# 03_ZIGBEE.net
KiCad netlist of a schematic drawn in Altium Designer
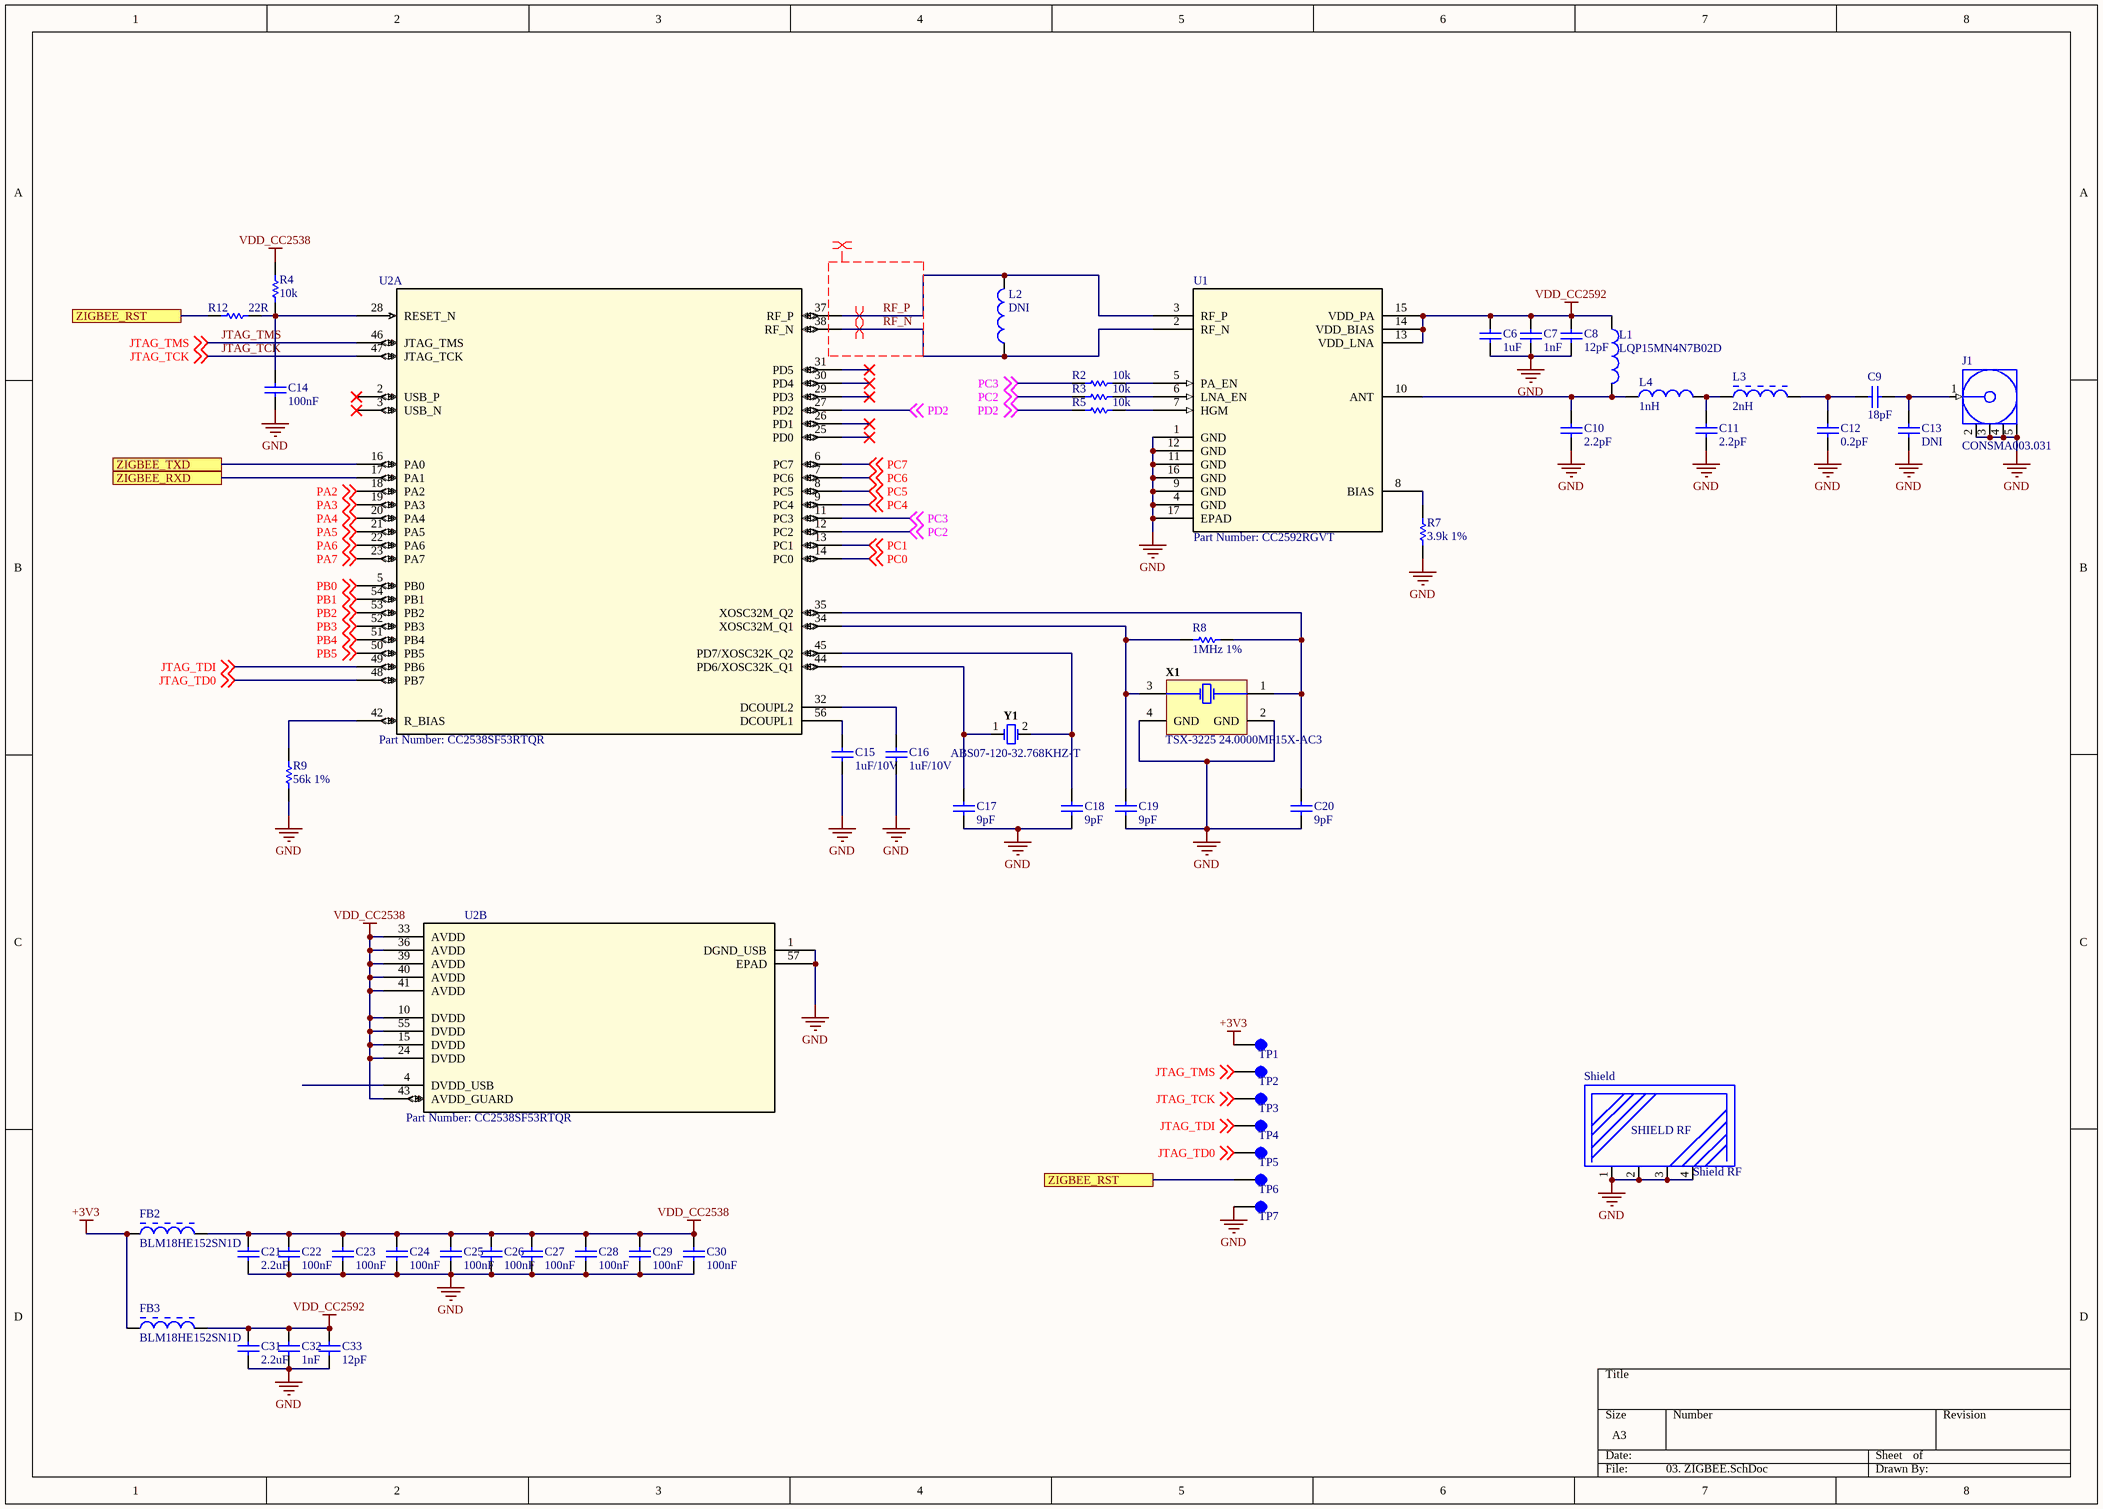
[diagram p0: 03. ZIGBEE.SchDoc]

(export (version "E")
  (design (tool "Eeschema 10.0.6"))
  (components
    (comp (ref "C6")
      (value "1uF")
      (footprint "CAPC1608X90X20NL10")
      (description "Chip Capacitor, 1 uF, +/- 10%, 50 V, -55 to 85 degC, 0603 (1608 Metric), RoHS, Tape and Reel")
      (fields
        (field (name "MANUFACTURER") "TDK")
        (field (name "PCN PART NUMBER") "MLCCPartNumberChange30/Nov/2012")
      )
      (libsource (lib "Altium Content Vault") (part "CAP-NP-2"))
    )
    (comp (ref "C7")
      (value "1nF")
      (footprint "CAPC1005X55X25NL05T10")
      (fields (field (name "PART NUMBER") "GRM1555C1H102JA01D") (field (name "MANUFACTURER") "Murata"))
      (libsource (lib "Altium Content Vault") (part "CAP"))
    )
    (comp (ref "C8")
      (value "12pF")
      (footprint "CAPC1005X55X25NL05T10")
      (fields (field (name "PART NUMBER") "GRM1555C1H120GA01D") (field (name "MANUFACTURER") "Murata"))
      (libsource (lib "Altium Content Vault") (part "CAP"))
    )
    (comp (ref "C9")
      (value "18pF")
      (footprint "CAPC1005X55X25NL05T10")
      (fields (field (name "PART NUMBER") "GJM1555C1H180GB01D") (field (name "MANUFACTURER") "Murata"))
      (libsource (lib "Altium Content Vault") (part "CAP"))
    )
    (comp (ref "C10")
      (value "2.2pF")
      (footprint "CAPC1005X55X25NL05T10")
      (fields (field (name "PART NUMBER") "GJM1555C1H2R2BB01D") (field (name "MANUFACTURER") "Murata"))
      (libsource (lib "Altium Content Vault") (part "CAP"))
    )
    (comp (ref "C11")
      (value "2.2pF")
      (footprint "CAPC1005X55X25NL05T10")
      (fields (field (name "PART NUMBER") "GJM1555C1H2R2BB01D") (field (name "MANUFACTURER") "Murata"))
      (libsource (lib "Altium Content Vault") (part "CAP"))
    )
    (comp (ref "C12")
      (value "0.2pF")
      (footprint "CAPC1005X55X25NL05T10")
      (fields (field (name "PART NUMBER") "GRM1555C1HR20WA01D") (field (name "MANUFACTURER") "Murata"))
      (libsource (lib "Altium Content Vault") (part "CAP"))
    )
    (comp (ref "C13")
      (value "DNI")
      (footprint "CAPC1005X55X25NL05T10")
      (fields (field (name "PART NUMBER") "GJM1555C1H180GB01D") (field (name "MANUFACTURER") "Murata"))
      (libsource (lib "Altium Content Vault") (part "CAP"))
    )
    (comp (ref "C14")
      (value "100nF")
      (footprint "CAPC1005X56X25NL10T15")
      (fields
        (field (name "MANUFACTURER") "AVX Interconnect / Elco")
        (field (name "PART NUMBER") "04026D104KAT2A")
      )
      (libsource (lib "Altium Content Vault") (part "CAP"))
    )
    (comp (ref "C15")
      (value "1uF/10V")
      (footprint "CAPC1005X55X25NL05T10")
      (fields (field (name "PART NUMBER") "GRM155R61A105KE15D") (field (name "MANUFACTURER") "Murata"))
      (libsource (lib "Altium Content Vault") (part "CAP"))
    )
    (comp (ref "C16")
      (value "1uF/10V")
      (footprint "CAPC1005X55X25NL05T10")
      (fields (field (name "PART NUMBER") "GRM155R61A105KE15D") (field (name "MANUFACTURER") "Murata"))
      (libsource (lib "Altium Content Vault") (part "CAP"))
    )
    (comp (ref "C17")
      (value "9pF")
      (footprint "CAPC1005X55X25NL05T10")
      (fields (field (name "PART NUMBER") "GJM1555C1H9R0CB01D") (field (name "MANUFACTURER") "Murata"))
      (libsource (lib "Altium Content Vault") (part "CAP"))
    )
    (comp (ref "C18")
      (value "9pF")
      (footprint "CAPC1005X55X25NL05T10")
      (fields (field (name "PART NUMBER") "GJM1555C1H9R0CB01D") (field (name "MANUFACTURER") "Murata"))
      (libsource (lib "Altium Content Vault") (part "CAP"))
    )
    (comp (ref "C19")
      (value "9pF")
      (footprint "CAPC1005X55X25NL05T10")
      (fields (field (name "PART NUMBER") "GJM1555C1H9R0CB01D") (field (name "MANUFACTURER") "Murata"))
      (libsource (lib "Altium Content Vault") (part "CAP"))
    )
    (comp (ref "C20")
      (value "9pF")
      (footprint "CAPC1005X55X25NL05T10")
      (fields (field (name "PART NUMBER") "GJM1555C1H9R0CB01D") (field (name "MANUFACTURER") "Murata"))
      (libsource (lib "Altium Content Vault") (part "CAP"))
    )
    (comp (ref "C21")
      (value "2.2uF")
      (footprint "CAPC1608X90X35NL10T15")
      (fields (field (name "MANUFACTURER") "Murata") (field (name "PART NUMBER") "GCM188R70J225KE22D"))
      (libsource (lib "Altium Content Vault") (part "CAP"))
    )
    (comp (ref "C22")
      (value "100nF")
      (footprint "CAPC1005X56X25NL10T15")
      (fields
        (field (name "MANUFACTURER") "AVX Interconnect / Elco")
        (field (name "PART NUMBER") "04026D104KAT2A")
      )
      (libsource (lib "Altium Content Vault") (part "CAP"))
    )
    (comp (ref "C23")
      (value "100nF")
      (footprint "CAPC1005X56X25NL10T15")
      (fields
        (field (name "MANUFACTURER") "AVX Interconnect / Elco")
        (field (name "PART NUMBER") "04026D104KAT2A")
      )
      (libsource (lib "Altium Content Vault") (part "CAP"))
    )
    (comp (ref "C24")
      (value "100nF")
      (footprint "CAPC1005X56X25NL10T15")
      (fields
        (field (name "MANUFACTURER") "AVX Interconnect / Elco")
        (field (name "PART NUMBER") "04026D104KAT2A")
      )
      (libsource (lib "Altium Content Vault") (part "CAP"))
    )
    (comp (ref "C25")
      (value "100nF")
      (footprint "CAPC1005X56X25NL10T15")
      (fields
        (field (name "MANUFACTURER") "AVX Interconnect / Elco")
        (field (name "PART NUMBER") "04026D104KAT2A")
      )
      (libsource (lib "Altium Content Vault") (part "CAP"))
    )
    (comp (ref "C26")
      (value "100nF")
      (footprint "CAPC1005X56X25NL10T15")
      (fields
        (field (name "MANUFACTURER") "AVX Interconnect / Elco")
        (field (name "PART NUMBER") "04026D104KAT2A")
      )
      (libsource (lib "Altium Content Vault") (part "CAP"))
    )
    (comp (ref "C27")
      (value "100nF")
      (footprint "CAPC1005X56X25NL10T15")
      (fields
        (field (name "MANUFACTURER") "AVX Interconnect / Elco")
        (field (name "PART NUMBER") "04026D104KAT2A")
      )
      (libsource (lib "Altium Content Vault") (part "CAP"))
    )
    (comp (ref "C28")
      (value "100nF")
      (footprint "CAPC1005X56X25NL10T15")
      (fields
        (field (name "MANUFACTURER") "AVX Interconnect / Elco")
        (field (name "PART NUMBER") "04026D104KAT2A")
      )
      (libsource (lib "Altium Content Vault") (part "CAP"))
    )
    (comp (ref "C29")
      (value "100nF")
      (footprint "CAPC1005X56X25NL10T15")
      (fields
        (field (name "MANUFACTURER") "AVX Interconnect / Elco")
        (field (name "PART NUMBER") "04026D104KAT2A")
      )
      (libsource (lib "Altium Content Vault") (part "CAP"))
    )
    (comp (ref "C30")
      (value "100nF")
      (footprint "CAPC1005X56X25NL10T15")
      (fields
        (field (name "MANUFACTURER") "AVX Interconnect / Elco")
        (field (name "PART NUMBER") "04026D104KAT2A")
      )
      (libsource (lib "Altium Content Vault") (part "CAP"))
    )
    (comp (ref "C31")
      (value "2.2uF")
      (footprint "CAPC1608X90X35NL10T15")
      (fields (field (name "MANUFACTURER") "Murata") (field (name "PART NUMBER") "GCM188R70J225KE22D"))
      (libsource (lib "Altium Content Vault") (part "CAP"))
    )
    (comp (ref "C32")
      (value "1nF")
      (footprint "CAPC1005X55X25NL05T10")
      (fields (field (name "PART NUMBER") "GRM1555C1H102JA01D") (field (name "MANUFACTURER") "Murata"))
      (libsource (lib "Altium Content Vault") (part "CAP"))
    )
    (comp (ref "C33")
      (value "12pF")
      (footprint "CAPC1005X55X25NL05T10")
      (fields (field (name "PART NUMBER") "GRM1555C1H120GA01D") (field (name "MANUFACTURER") "Murata"))
      (libsource (lib "Altium Content Vault") (part "CAP"))
    )
    (comp (ref "FB2")
      (value "BLM18HE152SN1D")
      (footprint "MURA-BLM18-RF-H4-CHIP-2_V")
      (fields (field (name "MANUFACTURER") "Murata"))
      (libsource (lib "Altium Content Vault") (part "MURA-FB-2"))
    )
    (comp (ref "FB3")
      (value "BLM18HE152SN1D")
      (footprint "MURA-BLM18-RF-H4-CHIP-2_V")
      (fields (field (name "MANUFACTURER") "Murata"))
      (libsource (lib "Altium Content Vault") (part "MURA-FB-2"))
    )
    (comp (ref "J1")
      (value "CONSMA003.031")
      (footprint "CON-SMA-EDGE031")
      (description "SMA Female Edge Mount Connector for 0.031\" Thick Board")
      (libsource (lib "Altium Content Vault") (part "CN-1P-F-RF5"))
    )
    (comp (ref "L1")
      (value "LQP15MN4N7B02D")
      (footprint "INDC1005X45X25LL10T10")
      (description "Chip Inductor, 4.7 nH, +/- 0.1 nH, 160 mA, -40 to 85 degC, 0402 (1005 Metric), RoHS, Tape and Reel")
      (fields (field (name "MANUFACTURER") "Murata") (field (name "TOLERANCE") "0.1nH"))
      (libsource (lib "Altium Content Vault") (part "IND-2"))
    )
    (comp (ref "L2")
      (value "DNI")
      (footprint "INDC1005X45X25NL10T10")
      (description "Chip Inductor, 1.8 nH, +/- 0.1 nH, 280 mA, -40 to 85 degC, 0402 (1005 Metric), RoHS, Tape and Reel")
      (fields (field (name "MANUFACTURER") "Murata"))
      (libsource (lib "Altium Content Vault") (part "IND-2"))
    )
    (comp (ref "L3")
      (value "2nH")
      (footprint "MURA-IND0402_V")
      (fields (field (name "MANUFACTURER") "Murata") (field (name "PARTNUMBER") "LQG15HS2N0S02D"))
      (libsource (lib "Altium Content Vault") (part "MURA-INDC-2"))
    )
    (comp (ref "L4")
      (value "1nH")
      (footprint "INDC1005X45X25NL10T10")
      (description "Chip Inductor, 1 nH, +/- 0.1 nH, 400 mA, -40 to 85 degC, 0402 (1005 Metric), RoHS, Tape and Reel")
      (fields (field (name "PARTNUMBER") "LQP15MN1N0B02D"))
      (libsource (lib "Altium Content Vault") (part "IND-2"))
    )
    (comp (ref "R2")
      (value "10k")
      (footprint "RESC1005X40X25NL05T05")
      (fields (field (name "MANUFACTURER") "Vishay Dale") (field (name "PART NUMBER") "CRCW040210K0FKED"))
      (libsource (lib "Altium Content Vault") (part "RES"))
    )
    (comp (ref "R3")
      (value "10k")
      (footprint "RESC1005X40X25NL05T05")
      (fields (field (name "MANUFACTURER") "Vishay Dale") (field (name "PART NUMBER") "CRCW040210K0FKED"))
      (libsource (lib "Altium Content Vault") (part "RES"))
    )
    (comp (ref "R4")
      (value "10k")
      (footprint "RESC1005X40X25NL05T05")
      (fields (field (name "MANUFACTURER") "Vishay Dale") (field (name "PART NUMBER") "CRCW040210K0FKED"))
      (libsource (lib "Altium Content Vault") (part "RES"))
    )
    (comp (ref "R5")
      (value "10k")
      (footprint "RESC1005X40X25NL05T05")
      (fields (field (name "MANUFACTURER") "Vishay Dale") (field (name "PART NUMBER") "CRCW040210K0FKED"))
      (libsource (lib "Altium Content Vault") (part "RES"))
    )
    (comp (ref "R7")
      (value "3.9k 1%")
      (footprint "RESC1005X40X25NL05T05")
      (fields (field (name "MANUFACTURER") "Vishay Dale") (field (name "PART NUMBER") "CRCW04023K90FKED"))
      (libsource (lib "Altium Content Vault") (part "RES"))
    )
    (comp (ref "R8")
      (value "1MHz 1%")
      (footprint "RESC1005X40X25NL05T05")
      (fields (field (name "PART NUMBER") "CRCW04020000Z0ED") (field (name "MANUFACTURER") "Vishay Dale"))
      (libsource (lib "Altium Content Vault") (part "RES"))
    )
    (comp (ref "R9")
      (value "56k 1%")
      (footprint "RESC1005X40X25NL05T05")
      (fields (field (name "PART NUMBER") "CRCW040256K0FKED") (field (name "MANUFACTURER") "Vishay Dale"))
      (libsource (lib "Altium Content Vault") (part "RES"))
    )
    (comp (ref "R12")
      (value "22R")
      (footprint "RESC1005X40X25LL05T05")
      (description "Chip Resistor, 22 Ohm, +/- 1%, 0.1 W, -55 to 155 degC, 0402 (1005 Metric), RoHS, Tape and Reel")
      (fields (field (name "PARTNUMBER") "ERJ-2RKF22R0X") (field (name "TOLERANCE") "1%"))
      (libsource (lib "AM3358_DEV_BOARD") (part "RES-2"))
    )
    (comp (ref "Shield")
      (value "Shield RF")
      (footprint "NSTRFShield")
      (libsource (lib "SyTungNguyen") (part "Shield RF"))
    )
    (comp (ref "TP1") (value "Test Point") (footprint "TP") (libsource (lib "SyTungNguyen") (part "TP")))
    (comp (ref "TP2") (value "Test Point") (footprint "TP") (libsource (lib "SyTungNguyen") (part "TP")))
    (comp (ref "TP3") (value "Test Point") (footprint "TP") (libsource (lib "SyTungNguyen") (part "TP")))
    (comp (ref "TP4") (value "Test Point") (footprint "TP") (libsource (lib "SyTungNguyen") (part "TP")))
    (comp (ref "TP5") (value "Test Point") (footprint "TP") (libsource (lib "SyTungNguyen") (part "TP")))
    (comp (ref "TP6") (value "Test Point") (footprint "TP") (libsource (lib "SyTungNguyen") (part "TP")))
    (comp (ref "TP7") (value "Test Point") (footprint "TP") (libsource (lib "SyTungNguyen") (part "TP")))
    (comp (ref "U1")
      (value "Part Number: CC2592RGVT")
      (footprint "QFN16_2P16X2P16")
      (description "No Description Available")
      (fields
        (field (name "MANUFACTURER_PART_NUMBER") "CC2592RGVT")
        (field (name "COPYRIGHT") "Copyright (C) 2018 Accelerated Designs. All rights reserved")
      )
      (libsource (lib "SyTungNguyen") (part "CC2592RGVT"))
    )
    (comp (ref "U2")
      (value "Part Number: CC2538SF53RTQR")
      (footprint "QFN56_6P7X6P7")
      (description "IC RF TxRx + MCU 802.15.4 6LoWPAN, Zigbee® 2.4GHz 56-VFQFN Exposed Pad")
      (fields
        (field (name "MANUFACTURER_PART_NUMBER") "CC2538SF53RTQR")
        (field (name "COPYRIGHT") "Copyright (C) 2018 Accelerated Designs. All rights reserved")
      )
      (libsource (lib "SyTungNguyen") (part "CC2538SF53RTQR"))
    )
    (comp (ref "X1")
      (value "TSX-3225 24.0000MF15X-AC3")
      (footprint "FP-NX3225SA-MFG")
      (description "MHz Range Crystal, 24 MHz, -40 to 85 degC, 4-Pin SMD, RoHS, Tape and Reel")
      (fields (field (name "TOLERANCE") "10PPM") (field (name "MANUFACTURER") "Epson"))
      (libsource (lib "AM3358_DEV_BOARD") (part "XTAL-1-3-4"))
    )
    (comp (ref "Y1")
      (value "ABS07-120-32.768KHZ-T")
      (footprint "ABRA-ABS07_A_V")
      (description "Tuning Fork Crystal, 32.768 KHz, +/- 20 ppm, -40 to 85 degC, 2-Pin SMD, RoHS, Tape and Reel")
      (fields (field (name "MANUFACTURER") "Abracon") (field (name "TOLERANCE") "20ppm"))
      (libsource (lib "Altium Content Vault") (part "XTAL-1-2-2"))
    )
  )
  (nets
    (net (code "1") (name "+3V3") (class "Default")
      (node (ref "FB2") (pin "1") (pinfunction "1_1") (pintype "passive"))
      (node (ref "FB3") (pin "1") (pinfunction "1_1") (pintype "passive"))
      (node (ref "TP1") (pin "1") (pintype "passive"))
    )
    (net (code "2") (name "/RF_N") (class "Default")
      (node (ref "L2") (pin "1") (pinfunction "1_1") (pintype "passive"))
      (node (ref "U1") (pin "2") (pinfunction "RF_N_2") (pintype "passive"))
      (node (ref "U2") (pin "38") (pinfunction "RF_N_38") (pintype "bidirectional"))
    )
    (net (code "3") (name "/RF_P") (class "Default")
      (node (ref "L2") (pin "2") (pinfunction "2_2") (pintype "passive"))
      (node (ref "U1") (pin "3") (pinfunction "RF_P_3") (pintype "passive"))
      (node (ref "U2") (pin "37") (pinfunction "RF_P_37") (pintype "bidirectional"))
    )
    (net (code "4") (name "/ZIGBEE_RST") (class "Default")
      (node (ref "R12") (pin "1") (pinfunction "1_1") (pintype "passive"))
      (node (ref "TP6") (pin "1") (pintype "passive"))
    )
    (net (code "5") (name "/ZIGBEE_RXD") (class "Default")
      (node (ref "U2") (pin "17") (pinfunction "PA1_17") (pintype "bidirectional"))
    )
    (net (code "6") (name "/ZIGBEE_TXD") (class "Default")
      (node (ref "U2") (pin "16") (pinfunction "PA0_16") (pintype "bidirectional"))
    )
    (net (code "7") (name "GND") (class "Default")
      (node (ref "C10") (pin "1") (pinfunction "1_1") (pintype "passive"))
      (node (ref "C11") (pin "1") (pinfunction "1_1") (pintype "passive"))
      (node (ref "C12") (pin "1") (pinfunction "1_1") (pintype "passive"))
      (node (ref "C13") (pin "1") (pinfunction "1_1") (pintype "passive"))
      (node (ref "C14") (pin "1") (pinfunction "1_1") (pintype "passive"))
      (node (ref "C15") (pin "1") (pinfunction "1_1") (pintype "passive"))
      (node (ref "C16") (pin "1") (pinfunction "1_1") (pintype "passive"))
      (node (ref "C17") (pin "1") (pinfunction "1_1") (pintype "passive"))
      (node (ref "C18") (pin "1") (pinfunction "1_1") (pintype "passive"))
      (node (ref "C19") (pin "1") (pinfunction "1_1") (pintype "passive"))
      (node (ref "C20") (pin "1") (pinfunction "1_1") (pintype "passive"))
      (node (ref "C21") (pin "1") (pinfunction "1_1") (pintype "passive"))
      (node (ref "C22") (pin "1") (pinfunction "1_1") (pintype "passive"))
      (node (ref "C23") (pin "1") (pinfunction "1_1") (pintype "passive"))
      (node (ref "C24") (pin "1") (pinfunction "1_1") (pintype "passive"))
      (node (ref "C25") (pin "1") (pinfunction "1_1") (pintype "passive"))
      (node (ref "C26") (pin "1") (pinfunction "1_1") (pintype "passive"))
      (node (ref "C27") (pin "1") (pinfunction "1_1") (pintype "passive"))
      (node (ref "C28") (pin "1") (pinfunction "1_1") (pintype "passive"))
      (node (ref "C29") (pin "1") (pinfunction "1_1") (pintype "passive"))
      (node (ref "C30") (pin "1") (pinfunction "1_1") (pintype "passive"))
      (node (ref "C31") (pin "1") (pinfunction "1_1") (pintype "passive"))
      (node (ref "C32") (pin "1") (pinfunction "1_1") (pintype "passive"))
      (node (ref "C33") (pin "1") (pinfunction "1_1") (pintype "passive"))
      (node (ref "C6") (pin "1") (pinfunction "1_1") (pintype "passive"))
      (node (ref "C7") (pin "1") (pinfunction "1_1") (pintype "passive"))
      (node (ref "C8") (pin "1") (pinfunction "1_1") (pintype "passive"))
      (node (ref "J1") (pin "2") (pinfunction "GND_2") (pintype "power_in"))
      (node (ref "J1") (pin "3") (pinfunction "GND_3") (pintype "power_in"))
      (node (ref "J1") (pin "4") (pinfunction "GND_4") (pintype "power_in"))
      (node (ref "J1") (pin "5") (pinfunction "GND_5") (pintype "power_in"))
      (node (ref "R7") (pin "1") (pinfunction "1_1") (pintype "passive"))
      (node (ref "R9") (pin "1") (pinfunction "1_1") (pintype "passive"))
      (node (ref "Shield") (pin "1") (pinfunction "1_1") (pintype "passive"))
      (node (ref "Shield") (pin "2") (pinfunction "2_2") (pintype "passive"))
      (node (ref "Shield") (pin "3") (pinfunction "3_3") (pintype "passive"))
      (node (ref "Shield") (pin "4") (pinfunction "4_4") (pintype "passive"))
      (node (ref "TP7") (pin "1") (pintype "passive"))
      (node (ref "U1") (pin "1") (pinfunction "GND_1") (pintype "power_in"))
      (node (ref "U1") (pin "11") (pinfunction "GND_11") (pintype "power_in"))
      (node (ref "U1") (pin "12") (pinfunction "GND_12") (pintype "power_in"))
      (node (ref "U1") (pin "16") (pinfunction "GND_16") (pintype "power_in"))
      (node (ref "U1") (pin "17") (pinfunction "EPAD_17") (pintype "passive"))
      (node (ref "U1") (pin "4") (pinfunction "GND_4") (pintype "power_in"))
      (node (ref "U1") (pin "9") (pinfunction "GND_9") (pintype "power_in"))
      (node (ref "U2") (pin "1") (pinfunction "DGND_USB_1") (pintype "power_in"))
      (node (ref "U2") (pin "57") (pinfunction "EPAD_57") (pintype "passive"))
      (node (ref "X1") (pin "2") (pinfunction "GND_2") (pintype "power_in"))
      (node (ref "X1") (pin "4") (pinfunction "GND_4") (pintype "power_in"))
    )
    (net (code "8") (name "JTAG_TCK") (class "Default")
      (node (ref "TP3") (pin "1") (pintype "passive"))
      (node (ref "U2") (pin "47") (pinfunction "JTAG_TCK_47") (pintype "bidirectional"))
    )
    (net (code "9") (name "JTAG_TD0") (class "Default")
      (node (ref "TP5") (pin "1") (pintype "passive"))
      (node (ref "U2") (pin "48") (pinfunction "PB7_48") (pintype "bidirectional"))
    )
    (net (code "10") (name "JTAG_TDI") (class "Default")
      (node (ref "TP4") (pin "1") (pintype "passive"))
      (node (ref "U2") (pin "49") (pinfunction "PB6_49") (pintype "bidirectional"))
    )
    (net (code "11") (name "JTAG_TMS") (class "Default")
      (node (ref "TP2") (pin "1") (pintype "passive"))
      (node (ref "U2") (pin "46") (pinfunction "JTAG_TMS_46") (pintype "bidirectional"))
    )
    (net (code "12") (name "Net-(C11-Pad2)") (class "Default")
      (node (ref "C11") (pin "2") (pinfunction "2_2") (pintype "passive"))
      (node (ref "L3") (pin "1") (pinfunction "1_1") (pintype "passive"))
      (node (ref "L4") (pin "2") (pinfunction "2_2") (pintype "passive"))
    )
    (net (code "13") (name "Net-(C12-Pad2)") (class "Default")
      (node (ref "C12") (pin "2") (pinfunction "2_2") (pintype "passive"))
      (node (ref "C9") (pin "1") (pinfunction "1_1") (pintype "passive"))
      (node (ref "L3") (pin "2") (pinfunction "2_2") (pintype "passive"))
    )
    (net (code "14") (name "Net-(J1-Signal)") (class "Default")
      (node (ref "C13") (pin "2") (pinfunction "2_2") (pintype "passive"))
      (node (ref "C9") (pin "2") (pinfunction "2_2") (pintype "passive"))
      (node (ref "J1") (pin "1") (pinfunction "Signal_1") (pintype "input"))
    )
    (net (code "15") (name "Net-(U1-ANT)") (class "Default")
      (node (ref "C10") (pin "2") (pinfunction "2_2") (pintype "passive"))
      (node (ref "L1") (pin "2") (pinfunction "2_2") (pintype "passive"))
      (node (ref "L4") (pin "1") (pinfunction "1_1") (pintype "passive"))
      (node (ref "U1") (pin "10") (pinfunction "ANT_10") (pintype "passive"))
    )
    (net (code "16") (name "Net-(U1-BIAS)") (class "Default")
      (node (ref "R7") (pin "2") (pinfunction "2_2") (pintype "passive"))
      (node (ref "U1") (pin "8") (pinfunction "BIAS_8") (pintype "passive"))
    )
    (net (code "17") (name "Net-(U1-HGM)") (class "Default")
      (node (ref "R5") (pin "2") (pinfunction "2_2") (pintype "passive"))
      (node (ref "U1") (pin "7") (pinfunction "HGM_7") (pintype "input"))
    )
    (net (code "18") (name "Net-(U1-LNA_EN)") (class "Default")
      (node (ref "R3") (pin "2") (pinfunction "2_2") (pintype "passive"))
      (node (ref "U1") (pin "6") (pinfunction "LNA_EN_6") (pintype "input"))
    )
    (net (code "19") (name "Net-(U1-PA_EN)") (class "Default")
      (node (ref "R2") (pin "2") (pinfunction "2_2") (pintype "passive"))
      (node (ref "U1") (pin "5") (pinfunction "PA_EN_5") (pintype "input"))
    )
    (net (code "20") (name "Net-(U2A-DCOUPL1)") (class "Default")
      (node (ref "C15") (pin "2") (pinfunction "2_2") (pintype "passive"))
      (node (ref "U2") (pin "56") (pinfunction "DCOUPL1_56") (pintype "power_in"))
    )
    (net (code "21") (name "Net-(U2A-DCOUPL2)") (class "Default")
      (node (ref "C16") (pin "2") (pinfunction "2_2") (pintype "passive"))
      (node (ref "U2") (pin "32") (pinfunction "DCOUPL2_32") (pintype "power_in"))
    )
    (net (code "22") (name "Net-(U2A-PD6{slash}XOSC32K_Q1)") (class "Default")
      (node (ref "C17") (pin "2") (pinfunction "2_2") (pintype "passive"))
      (node (ref "U2") (pin "44") (pinfunction "PD6/XOSC32K_Q1_44") (pintype "bidirectional"))
      (node (ref "Y1") (pin "1") (pinfunction "1_1") (pintype "passive"))
    )
    (net (code "23") (name "Net-(U2A-PD7{slash}XOSC32K_Q2)") (class "Default")
      (node (ref "C18") (pin "2") (pinfunction "2_2") (pintype "passive"))
      (node (ref "U2") (pin "45") (pinfunction "PD7/XOSC32K_Q2_45") (pintype "bidirectional"))
      (node (ref "Y1") (pin "2") (pinfunction "2_2") (pintype "passive"))
    )
    (net (code "24") (name "Net-(U2A-RESET_N)") (class "Default")
      (node (ref "C14") (pin "2") (pinfunction "2_2") (pintype "passive"))
      (node (ref "R12") (pin "2") (pinfunction "2_2") (pintype "passive"))
      (node (ref "R4") (pin "1") (pinfunction "1_1") (pintype "passive"))
      (node (ref "U2") (pin "28") (pinfunction "RESET_N_28") (pintype "input"))
    )
    (net (code "25") (name "Net-(U2A-R_BIAS)") (class "Default")
      (node (ref "R9") (pin "2") (pinfunction "2_2") (pintype "passive"))
      (node (ref "U2") (pin "42") (pinfunction "R_BIAS_42") (pintype "bidirectional"))
    )
    (net (code "26") (name "Net-(U2A-XOSC32M_Q1)") (class "Default")
      (node (ref "C19") (pin "2") (pinfunction "2_2") (pintype "passive"))
      (node (ref "R8") (pin "1") (pinfunction "1_1") (pintype "passive"))
      (node (ref "U2") (pin "34") (pinfunction "XOSC32M_Q1_34") (pintype "bidirectional"))
      (node (ref "X1") (pin "3") (pinfunction "X2_3") (pintype "passive"))
    )
    (net (code "27") (name "Net-(U2A-XOSC32M_Q2)") (class "Default")
      (node (ref "C20") (pin "2") (pinfunction "2_2") (pintype "passive"))
      (node (ref "R8") (pin "2") (pinfunction "2_2") (pintype "passive"))
      (node (ref "U2") (pin "35") (pinfunction "XOSC32M_Q2_35") (pintype "bidirectional"))
      (node (ref "X1") (pin "1") (pinfunction "X1_1") (pintype "passive"))
    )
    (net (code "28") (name "PA2") (class "Default")
      (node (ref "U2") (pin "18") (pinfunction "PA2_18") (pintype "bidirectional"))
    )
    (net (code "29") (name "PA3") (class "Default")
      (node (ref "U2") (pin "19") (pinfunction "PA3_19") (pintype "bidirectional"))
    )
    (net (code "30") (name "PA4") (class "Default")
      (node (ref "U2") (pin "20") (pinfunction "PA4_20") (pintype "bidirectional"))
    )
    (net (code "31") (name "PA5") (class "Default")
      (node (ref "U2") (pin "21") (pinfunction "PA5_21") (pintype "bidirectional"))
    )
    (net (code "32") (name "PA6") (class "Default")
      (node (ref "U2") (pin "22") (pinfunction "PA6_22") (pintype "bidirectional"))
    )
    (net (code "33") (name "PA7") (class "Default")
      (node (ref "U2") (pin "23") (pinfunction "PA7_23") (pintype "bidirectional"))
    )
    (net (code "34") (name "PB0") (class "Default")
      (node (ref "U2") (pin "5") (pinfunction "PB0_5") (pintype "bidirectional"))
    )
    (net (code "35") (name "PB1") (class "Default")
      (node (ref "U2") (pin "54") (pinfunction "PB1_54") (pintype "bidirectional"))
    )
    (net (code "36") (name "PB2") (class "Default")
      (node (ref "U2") (pin "53") (pinfunction "PB2_53") (pintype "bidirectional"))
    )
    (net (code "37") (name "PB3") (class "Default")
      (node (ref "U2") (pin "52") (pinfunction "PB3_52") (pintype "bidirectional"))
    )
    (net (code "38") (name "PB4") (class "Default")
      (node (ref "U2") (pin "51") (pinfunction "PB4_51") (pintype "bidirectional"))
    )
    (net (code "39") (name "PB5") (class "Default")
      (node (ref "U2") (pin "50") (pinfunction "PB5_50") (pintype "bidirectional"))
    )
    (net (code "40") (name "PC0") (class "Default")
      (node (ref "U2") (pin "14") (pinfunction "PC0_14") (pintype "bidirectional"))
    )
    (net (code "41") (name "PC1") (class "Default")
      (node (ref "U2") (pin "13") (pinfunction "PC1_13") (pintype "bidirectional"))
    )
    (net (code "42") (name "PC2") (class "Default")
      (node (ref "R3") (pin "1") (pinfunction "1_1") (pintype "passive"))
      (node (ref "U2") (pin "12") (pinfunction "PC2_12") (pintype "bidirectional"))
    )
    (net (code "43") (name "PC3") (class "Default")
      (node (ref "R2") (pin "1") (pinfunction "1_1") (pintype "passive"))
      (node (ref "U2") (pin "11") (pinfunction "PC3_11") (pintype "bidirectional"))
    )
    (net (code "44") (name "PC4") (class "Default")
      (node (ref "U2") (pin "9") (pinfunction "PC4_9") (pintype "bidirectional"))
    )
    (net (code "45") (name "PC5") (class "Default")
      (node (ref "U2") (pin "8") (pinfunction "PC5_8") (pintype "bidirectional"))
    )
    (net (code "46") (name "PC6") (class "Default")
      (node (ref "U2") (pin "7") (pinfunction "PC6_7") (pintype "bidirectional"))
    )
    (net (code "47") (name "PC7") (class "Default")
      (node (ref "U2") (pin "6") (pinfunction "PC7_6") (pintype "bidirectional"))
    )
    (net (code "48") (name "PD2") (class "Default")
      (node (ref "R5") (pin "1") (pinfunction "1_1") (pintype "passive"))
      (node (ref "U2") (pin "27") (pinfunction "PD2_27") (pintype "bidirectional"))
    )
    (net (code "49") (name "VDD_CC2538") (class "Default")
      (node (ref "C21") (pin "2") (pinfunction "2_2") (pintype "passive"))
      (node (ref "C22") (pin "2") (pinfunction "2_2") (pintype "passive"))
      (node (ref "C23") (pin "2") (pinfunction "2_2") (pintype "passive"))
      (node (ref "C24") (pin "2") (pinfunction "2_2") (pintype "passive"))
      (node (ref "C25") (pin "2") (pinfunction "2_2") (pintype "passive"))
      (node (ref "C26") (pin "2") (pinfunction "2_2") (pintype "passive"))
      (node (ref "C27") (pin "2") (pinfunction "2_2") (pintype "passive"))
      (node (ref "C28") (pin "2") (pinfunction "2_2") (pintype "passive"))
      (node (ref "C29") (pin "2") (pinfunction "2_2") (pintype "passive"))
      (node (ref "C30") (pin "2") (pinfunction "2_2") (pintype "passive"))
      (node (ref "FB2") (pin "2") (pinfunction "2_2") (pintype "passive"))
      (node (ref "R4") (pin "2") (pinfunction "2_2") (pintype "passive"))
      (node (ref "U2") (pin "10") (pinfunction "DVDD_10") (pintype "power_in"))
      (node (ref "U2") (pin "15") (pinfunction "DVDD_15") (pintype "power_in"))
      (node (ref "U2") (pin "24") (pinfunction "DVDD_24") (pintype "power_in"))
      (node (ref "U2") (pin "33") (pinfunction "AVDD_33") (pintype "power_in"))
      (node (ref "U2") (pin "36") (pinfunction "AVDD_36") (pintype "power_in"))
      (node (ref "U2") (pin "39") (pinfunction "AVDD_39") (pintype "power_in"))
      (node (ref "U2") (pin "40") (pinfunction "AVDD_40") (pintype "power_in"))
      (node (ref "U2") (pin "41") (pinfunction "AVDD_41") (pintype "power_in"))
      (node (ref "U2") (pin "43") (pinfunction "AVDD_GUARD_43") (pintype "bidirectional"))
      (node (ref "U2") (pin "55") (pinfunction "DVDD_55") (pintype "power_in"))
    )
    (net (code "50") (name "VDD_CC2592") (class "Default")
      (node (ref "C31") (pin "2") (pinfunction "2_2") (pintype "passive"))
      (node (ref "C32") (pin "2") (pinfunction "2_2") (pintype "passive"))
      (node (ref "C33") (pin "2") (pinfunction "2_2") (pintype "passive"))
      (node (ref "C6") (pin "2") (pinfunction "2_2") (pintype "passive"))
      (node (ref "C7") (pin "2") (pinfunction "2_2") (pintype "passive"))
      (node (ref "C8") (pin "2") (pinfunction "2_2") (pintype "passive"))
      (node (ref "FB3") (pin "2") (pinfunction "2_2") (pintype "passive"))
      (node (ref "L1") (pin "1") (pinfunction "1_1") (pintype "passive"))
      (node (ref "U1") (pin "13") (pinfunction "VDD_LNA_13") (pintype "power_in"))
      (node (ref "U1") (pin "14") (pinfunction "VDD_BIAS_14") (pintype "power_in"))
      (node (ref "U1") (pin "15") (pinfunction "VDD_PA_15") (pintype "power_in"))
    )
    (net (code "51") (name "unconnected-(U2A-PD0-Pad25)") (class "Default")
      (node (ref "U2") (pin "25") (pinfunction "PD0_25") (pintype "bidirectional+no_connect"))
    )
    (net (code "52") (name "unconnected-(U2A-PD1-Pad26)") (class "Default")
      (node (ref "U2") (pin "26") (pinfunction "PD1_26") (pintype "bidirectional+no_connect"))
    )
    (net (code "53") (name "unconnected-(U2A-PD3-Pad29)") (class "Default")
      (node (ref "U2") (pin "29") (pinfunction "PD3_29") (pintype "bidirectional+no_connect"))
    )
    (net (code "54") (name "unconnected-(U2A-PD4-Pad30)") (class "Default")
      (node (ref "U2") (pin "30") (pinfunction "PD4_30") (pintype "bidirectional+no_connect"))
    )
    (net (code "55") (name "unconnected-(U2A-PD5-Pad31)") (class "Default")
      (node (ref "U2") (pin "31") (pinfunction "PD5_31") (pintype "bidirectional+no_connect"))
    )
    (net (code "56") (name "unconnected-(U2A-USB_N-Pad3)") (class "Default")
      (node (ref "U2") (pin "3") (pinfunction "USB_N_3") (pintype "bidirectional+no_connect"))
    )
    (net (code "57") (name "unconnected-(U2A-USB_P-Pad2)") (class "Default")
      (node (ref "U2") (pin "2") (pinfunction "USB_P_2") (pintype "bidirectional+no_connect"))
    )
    (net (code "58") (name "unconnected-(U2B-DVDD_USB-Pad4)") (class "Default")
      (node (ref "U2") (pin "4") (pinfunction "DVDD_USB_4") (pintype "power_in"))
    )
  )
)
